# SINGLE.net
KiCad netlist of a schematic drawn in EAGLE
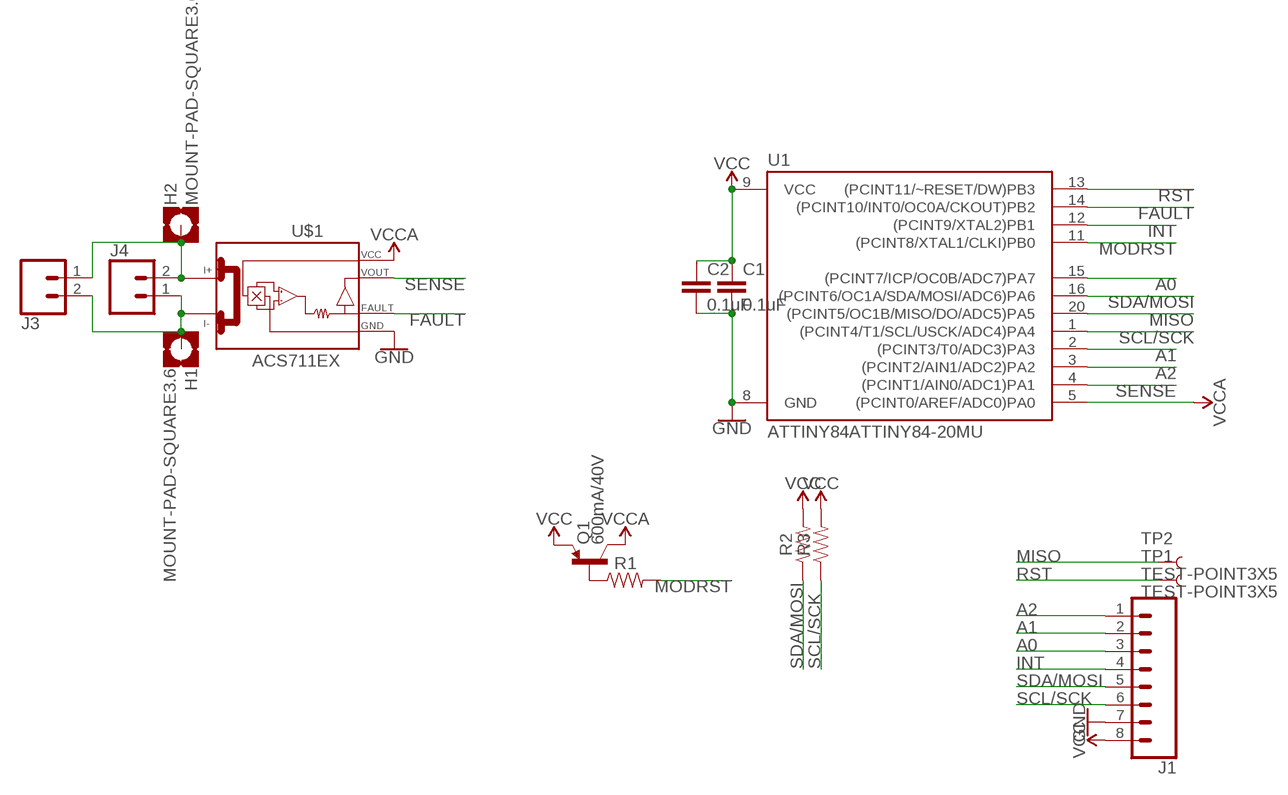
[diagram p0: schematic, sheet 1]

(export (version "E")
  (design (tool "Eeschema 10.0.6"))
  (components
    (comp (ref "C1")
      (value "0.1uF")
      (footprint "eagle-import:0603")
      (libsource (lib "eagle-import") (part "0.1UF-0603-25V-5%"))
    )
    (comp (ref "C2")
      (value "0.1uF")
      (footprint "eagle-import:0603")
      (libsource (lib "eagle-import") (part "0.1UF-0603-25V-5%"))
    )
    (comp (ref "H1")
      (value "MOUNT-PAD-SQUARE3.6")
      (footprint "eagle-import:3,6-PAD-SQUARE")
      (libsource (lib "eagle-import") (part "MOUNT-PAD-SQUARE3.6"))
    )
    (comp (ref "H2")
      (value "MOUNT-PAD-SQUARE3.6")
      (footprint "eagle-import:3,6-PAD-SQUARE")
      (libsource (lib "eagle-import") (part "MOUNT-PAD-SQUARE3.6"))
    )
    (comp (ref "J1")
      (value "CONN_08NO_SILK_FEMALE_PTH")
      (footprint "eagle-import:1X08_NO_SILK")
      (libsource (lib "eagle-import") (part "CONN_08NO_SILK_FEMALE_PTH"))
    )
    (comp (ref "J3")
      (value "CONN_025MM")
      (footprint "eagle-import:SCREWTERMINAL-5MM-2")
      (libsource (lib "eagle-import") (part "CONN_025MM"))
    )
    (comp (ref "J4")
      (value "CONN_02")
      (footprint "eagle-import:1X02")
      (libsource (lib "eagle-import") (part "CONN_02"))
    )
    (comp (ref "Q1")
      (value "600mA/40V")
      (footprint "eagle-import:SOT23-3")
      (libsource (lib "eagle-import") (part "TRANS_PNP-MMBT4403"))
    )
    (comp (ref "R1")
      (value "RESISTOR0603")
      (footprint "eagle-import:0603")
      (libsource (lib "eagle-import") (part "RESISTOR0603"))
    )
    (comp (ref "R2")
      (value "RESISTOR0603")
      (footprint "eagle-import:0603")
      (libsource (lib "eagle-import") (part "RESISTOR0603"))
    )
    (comp (ref "R3")
      (value "RESISTOR0603")
      (footprint "eagle-import:0603")
      (libsource (lib "eagle-import") (part "RESISTOR0603"))
    )
    (comp (ref "TP1")
      (value "TEST-POINT3X5")
      (footprint "eagle-import:PAD.03X.05")
      (libsource (lib "eagle-import") (part "TEST-POINT3X5"))
    )
    (comp (ref "TP2")
      (value "TEST-POINT3X5")
      (footprint "eagle-import:PAD.03X.05")
      (libsource (lib "eagle-import") (part "TEST-POINT3X5"))
    )
    (comp (ref "U$1")
      (value "ACS711EX")
      (footprint "eagle-import:QFN-12EX_3X3")
      (libsource (lib "eagle-import") (part "ACS711EX"))
    )
    (comp (ref "U1")
      (value "ATTINY84ATTINY84-20MU")
      (footprint "eagle-import:QFN20")
      (libsource (lib "eagle-import") (part "ATTINY84ATTINY84-20MU"))
    )
  )
  (nets
    (net (code "1") (name "/A0") (class "Default")
      (node (ref "J1") (pin "3") (pinfunction "3_3") (pintype "passive"))
      (node (ref "U1") (pin "15") (pinfunction "(PCINT7/ICP/OC0B/ADC7)PA7_15") (pintype "bidirectional"))
    )
    (net (code "2") (name "/A1") (class "Default")
      (node (ref "J1") (pin "2") (pinfunction "2_2") (pintype "passive"))
      (node (ref "U1") (pin "2") (pinfunction "(PCINT3/T0/ADC3)PA3_2") (pintype "bidirectional"))
    )
    (net (code "3") (name "/A2") (class "Default")
      (node (ref "J1") (pin "1") (pinfunction "1_1") (pintype "passive"))
      (node (ref "U1") (pin "3") (pinfunction "(PCINT2/AIN1/ADC2)PA2_3") (pintype "bidirectional"))
    )
    (net (code "4") (name "/FAULT") (class "Default")
      (node (ref "U$1") (pin "P$4") (pinfunction "FAULT_P$4") (pintype "bidirectional"))
      (node (ref "U1") (pin "14") (pinfunction "(PCINT10/INT0/OC0A/CKOUT)PB2_14") (pintype "bidirectional"))
    )
    (net (code "5") (name "/INT") (class "Default")
      (node (ref "J1") (pin "4") (pinfunction "4_4") (pintype "passive"))
      (node (ref "U1") (pin "12") (pinfunction "(PCINT9/XTAL2)PB1_12") (pintype "bidirectional"))
    )
    (net (code "6") (name "/MISO") (class "Default")
      (node (ref "TP2") (pin "P$1") (pinfunction "1_P$1") (pintype "bidirectional"))
      (node (ref "U1") (pin "20") (pinfunction "(PCINT5/OC1B/MISO/DO/ADC5)PA5_20") (pintype "bidirectional"))
    )
    (net (code "7") (name "/MODRST") (class "Default")
      (node (ref "R1") (pin "2") (pinfunction "2_2") (pintype "passive"))
      (node (ref "U1") (pin "11") (pinfunction "(PCINT8/XTAL1/CLKI)PB0_11") (pintype "bidirectional"))
    )
    (net (code "8") (name "/RST") (class "Default")
      (node (ref "TP1") (pin "P$1") (pinfunction "1_P$1") (pintype "bidirectional"))
      (node (ref "U1") (pin "13") (pinfunction "(PCINT11/~{RESET/DW})PB3_13") (pintype "bidirectional"))
    )
    (net (code "9") (name "/SCL{slash}SCK") (class "Default")
      (node (ref "J1") (pin "6") (pinfunction "6_6") (pintype "passive"))
      (node (ref "R3") (pin "1") (pinfunction "1_1") (pintype "passive"))
      (node (ref "U1") (pin "1") (pinfunction "(PCINT4/T1/SCL/USCK/ADC4)PA4_1") (pintype "bidirectional"))
    )
    (net (code "10") (name "/SDA{slash}MOSI") (class "Default")
      (node (ref "J1") (pin "5") (pinfunction "5_5") (pintype "passive"))
      (node (ref "R2") (pin "1") (pinfunction "1_1") (pintype "passive"))
      (node (ref "U1") (pin "16") (pinfunction "(PCINT6/OC1A/SDA/MOSI/ADC6)PA6_16") (pintype "bidirectional"))
    )
    (net (code "11") (name "/SENSE") (class "Default")
      (node (ref "U$1") (pin "P$9") (pinfunction "VOUT_P$9") (pintype "output"))
      (node (ref "U1") (pin "4") (pinfunction "(PCINT1/AIN0/ADC1)PA1_4") (pintype "bidirectional"))
    )
    (net (code "12") (name "GND") (class "Default")
      (node (ref "C1") (pin "2") (pinfunction "2_2") (pintype "passive"))
      (node (ref "C2") (pin "2") (pinfunction "2_2") (pintype "passive"))
      (node (ref "J1") (pin "7") (pinfunction "7_7") (pintype "passive"))
      (node (ref "U$1") (pin "P$3") (pinfunction "GND_P$3") (pintype "power_in"))
      (node (ref "U1") (pin "8") (pinfunction "GND_8") (pintype "bidirectional"))
    )
    (net (code "13") (name "Net-(H1-MOUNT)") (class "Default")
      (node (ref "H1") (pin "B3,6") (pinfunction "MOUNT_B3,6") (pintype "passive"))
      (node (ref "J3") (pin "2") (pinfunction "2_2") (pintype "passive"))
      (node (ref "J4") (pin "1") (pinfunction "1_1") (pintype "passive"))
      (node (ref "U$1") (pin "P$2") (pinfunction "I-_1_P$2") (pintype "bidirectional"))
    )
    (net (code "14") (name "Net-(H2-MOUNT)") (class "Default")
      (node (ref "H2") (pin "B3,6") (pinfunction "MOUNT_B3,6") (pintype "passive"))
      (node (ref "J3") (pin "1") (pinfunction "1_1") (pintype "passive"))
      (node (ref "J4") (pin "2") (pinfunction "2_2") (pintype "passive"))
      (node (ref "U$1") (pin "P$1") (pinfunction "I+_1_P$1") (pintype "bidirectional"))
    )
    (net (code "15") (name "Net-(Q1-B)") (class "Default")
      (node (ref "Q1") (pin "1") (pinfunction "B_1") (pintype "passive"))
      (node (ref "R1") (pin "1") (pinfunction "1_1") (pintype "passive"))
    )
    (net (code "16") (name "VCC") (class "Default")
      (node (ref "C1") (pin "1") (pinfunction "1_1") (pintype "passive"))
      (node (ref "C2") (pin "1") (pinfunction "1_1") (pintype "passive"))
      (node (ref "J1") (pin "8") (pinfunction "8_8") (pintype "passive"))
      (node (ref "Q1") (pin "2") (pinfunction "E_2") (pintype "passive"))
      (node (ref "R2") (pin "2") (pinfunction "2_2") (pintype "passive"))
      (node (ref "R3") (pin "2") (pinfunction "2_2") (pintype "passive"))
      (node (ref "U1") (pin "9") (pinfunction "VCC_9") (pintype "bidirectional"))
    )
    (net (code "17") (name "VCCA") (class "Default")
      (node (ref "Q1") (pin "3") (pinfunction "C_3") (pintype "passive"))
      (node (ref "U$1") (pin "P$10") (pinfunction "VCC_P$10") (pintype "power_in"))
      (node (ref "U1") (pin "5") (pinfunction "(PCINT0/AREF/ADC0)PA0_5") (pintype "bidirectional"))
    )
  )
)
